# keypad.net
KiCad netlist of a schematic drawn in EAGLE
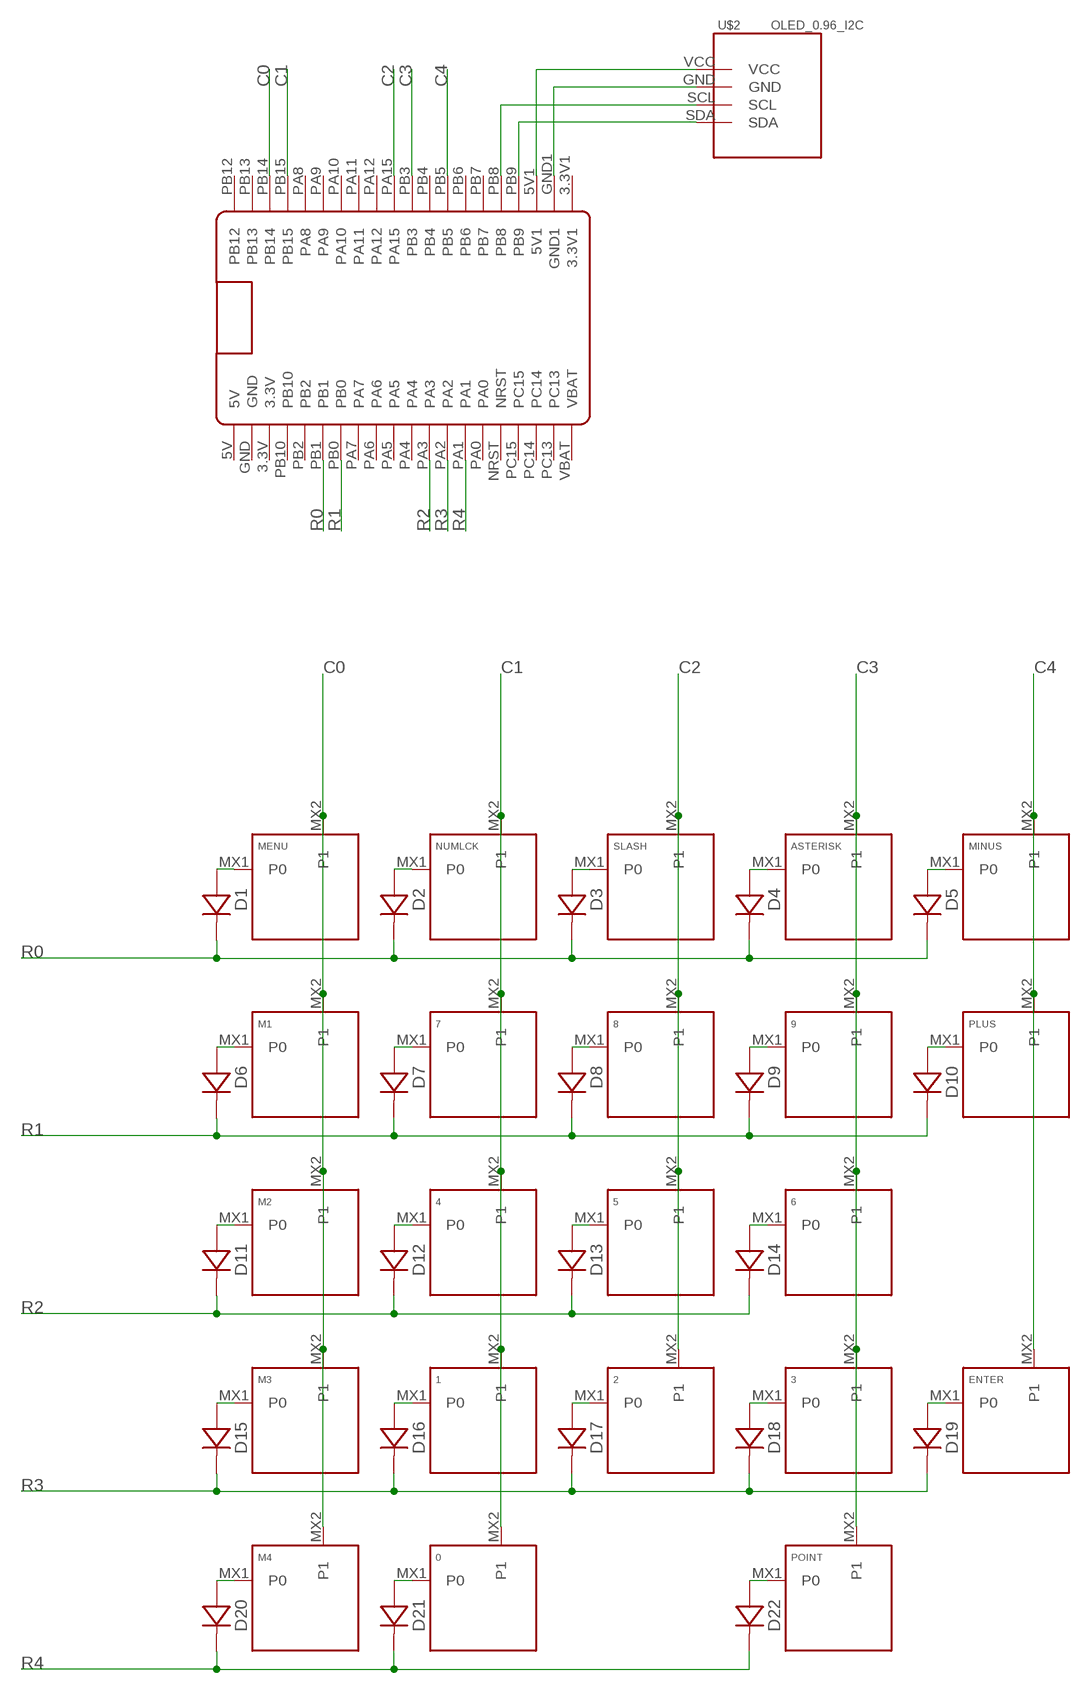
[diagram p0: schematic, sheet 1]

(export (version "E")
  (design (tool "Eeschema 10.0.6"))
  (components
    (comp (ref "0")
      (value "KEYSWITCH-PLAIN-MX-2U-FLIPPED")
      (footprint "eagle-import:MX-2U-FLIPPED")
      (libsource (lib "eagle-import") (part "KEYSWITCH-PLAIN-MX-2U-FLIPPED"))
    )
    (comp (ref "1")
      (value "KEYSWITCH-PLAIN-MX-1U")
      (footprint "eagle-import:MX-1U")
      (libsource (lib "eagle-import") (part "KEYSWITCH-PLAIN-MX-1U"))
    )
    (comp (ref "2")
      (value "KEYSWITCH-PLAIN-MX-1U")
      (footprint "eagle-import:MX-1U")
      (libsource (lib "eagle-import") (part "KEYSWITCH-PLAIN-MX-1U"))
    )
    (comp (ref "3")
      (value "KEYSWITCH-PLAIN-MX-1U")
      (footprint "eagle-import:MX-1U")
      (libsource (lib "eagle-import") (part "KEYSWITCH-PLAIN-MX-1U"))
    )
    (comp (ref "4")
      (value "KEYSWITCH-PLAIN-MX-1U")
      (footprint "eagle-import:MX-1U")
      (libsource (lib "eagle-import") (part "KEYSWITCH-PLAIN-MX-1U"))
    )
    (comp (ref "5")
      (value "KEYSWITCH-PLAIN-MX-1U")
      (footprint "eagle-import:MX-1U")
      (libsource (lib "eagle-import") (part "KEYSWITCH-PLAIN-MX-1U"))
    )
    (comp (ref "6")
      (value "KEYSWITCH-PLAIN-MX-1U")
      (footprint "eagle-import:MX-1U")
      (libsource (lib "eagle-import") (part "KEYSWITCH-PLAIN-MX-1U"))
    )
    (comp (ref "7")
      (value "KEYSWITCH-PLAIN-MX-1U")
      (footprint "eagle-import:MX-1U")
      (libsource (lib "eagle-import") (part "KEYSWITCH-PLAIN-MX-1U"))
    )
    (comp (ref "8")
      (value "KEYSWITCH-PLAIN-MX-1U")
      (footprint "eagle-import:MX-1U")
      (libsource (lib "eagle-import") (part "KEYSWITCH-PLAIN-MX-1U"))
    )
    (comp (ref "9")
      (value "KEYSWITCH-PLAIN-MX-1U")
      (footprint "eagle-import:MX-1U")
      (libsource (lib "eagle-import") (part "KEYSWITCH-PLAIN-MX-1U"))
    )
    (comp (ref "ASTERISK")
      (value "KEYSWITCH-PLAIN-MX-1U")
      (footprint "eagle-import:MX-1U")
      (libsource (lib "eagle-import") (part "KEYSWITCH-PLAIN-MX-1U"))
    )
    (comp (ref "D1")
      (value "DIODE-SOD-123")
      (footprint "eagle-import:SOD-123")
      (libsource (lib "eagle-import") (part "DIODE-SOD-123"))
    )
    (comp (ref "D2")
      (value "DIODE-SOD-123")
      (footprint "eagle-import:SOD-123")
      (libsource (lib "eagle-import") (part "DIODE-SOD-123"))
    )
    (comp (ref "D3")
      (value "DIODE-SOD-123")
      (footprint "eagle-import:SOD-123")
      (libsource (lib "eagle-import") (part "DIODE-SOD-123"))
    )
    (comp (ref "D4")
      (value "DIODE-SOD-123")
      (footprint "eagle-import:SOD-123")
      (libsource (lib "eagle-import") (part "DIODE-SOD-123"))
    )
    (comp (ref "D5")
      (value "DIODE-SOD-123")
      (footprint "eagle-import:SOD-123")
      (libsource (lib "eagle-import") (part "DIODE-SOD-123"))
    )
    (comp (ref "D6")
      (value "DIODE-SOD-123")
      (footprint "eagle-import:SOD-123")
      (libsource (lib "eagle-import") (part "DIODE-SOD-123"))
    )
    (comp (ref "D7")
      (value "DIODE-SOD-123")
      (footprint "eagle-import:SOD-123")
      (libsource (lib "eagle-import") (part "DIODE-SOD-123"))
    )
    (comp (ref "D8")
      (value "DIODE-SOD-123")
      (footprint "eagle-import:SOD-123")
      (libsource (lib "eagle-import") (part "DIODE-SOD-123"))
    )
    (comp (ref "D9")
      (value "DIODE-SOD-123")
      (footprint "eagle-import:SOD-123")
      (libsource (lib "eagle-import") (part "DIODE-SOD-123"))
    )
    (comp (ref "D10")
      (value "DIODE-SOD-123")
      (footprint "eagle-import:SOD-123")
      (libsource (lib "eagle-import") (part "DIODE-SOD-123"))
    )
    (comp (ref "D11")
      (value "DIODE-SOD-123")
      (footprint "eagle-import:SOD-123")
      (libsource (lib "eagle-import") (part "DIODE-SOD-123"))
    )
    (comp (ref "D12")
      (value "DIODE-SOD-123")
      (footprint "eagle-import:SOD-123")
      (libsource (lib "eagle-import") (part "DIODE-SOD-123"))
    )
    (comp (ref "D13")
      (value "DIODE-SOD-123")
      (footprint "eagle-import:SOD-123")
      (libsource (lib "eagle-import") (part "DIODE-SOD-123"))
    )
    (comp (ref "D14")
      (value "DIODE-SOD-123")
      (footprint "eagle-import:SOD-123")
      (libsource (lib "eagle-import") (part "DIODE-SOD-123"))
    )
    (comp (ref "D15")
      (value "DIODE-SOD-123")
      (footprint "eagle-import:SOD-123")
      (libsource (lib "eagle-import") (part "DIODE-SOD-123"))
    )
    (comp (ref "D16")
      (value "DIODE-SOD-123")
      (footprint "eagle-import:SOD-123")
      (libsource (lib "eagle-import") (part "DIODE-SOD-123"))
    )
    (comp (ref "D17")
      (value "DIODE-SOD-123")
      (footprint "eagle-import:SOD-123")
      (libsource (lib "eagle-import") (part "DIODE-SOD-123"))
    )
    (comp (ref "D18")
      (value "DIODE-SOD-123")
      (footprint "eagle-import:SOD-123")
      (libsource (lib "eagle-import") (part "DIODE-SOD-123"))
    )
    (comp (ref "D19")
      (value "DIODE-SOD-123")
      (footprint "eagle-import:SOD-123")
      (libsource (lib "eagle-import") (part "DIODE-SOD-123"))
    )
    (comp (ref "D20")
      (value "DIODE-SOD-123")
      (footprint "eagle-import:SOD-123")
      (libsource (lib "eagle-import") (part "DIODE-SOD-123"))
    )
    (comp (ref "D21")
      (value "DIODE-SOD-123")
      (footprint "eagle-import:SOD-123")
      (libsource (lib "eagle-import") (part "DIODE-SOD-123"))
    )
    (comp (ref "D22")
      (value "DIODE-SOD-123")
      (footprint "eagle-import:SOD-123")
      (libsource (lib "eagle-import") (part "DIODE-SOD-123"))
    )
    (comp (ref "ENTER")
      (value "KEYSWITCH-PLAIN-MX-2U-ROTATED")
      (footprint "eagle-import:MX-2U-ROTATED")
      (libsource (lib "eagle-import") (part "KEYSWITCH-PLAIN-MX-2U-ROTATED"))
    )
    (comp (ref "M1")
      (value "KEYSWITCH-PLAIN-MX-1U")
      (footprint "eagle-import:MX-1U")
      (libsource (lib "eagle-import") (part "KEYSWITCH-PLAIN-MX-1U"))
    )
    (comp (ref "M2")
      (value "KEYSWITCH-PLAIN-MX-1U")
      (footprint "eagle-import:MX-1U")
      (libsource (lib "eagle-import") (part "KEYSWITCH-PLAIN-MX-1U"))
    )
    (comp (ref "M3")
      (value "KEYSWITCH-PLAIN-MX-1U")
      (footprint "eagle-import:MX-1U")
      (libsource (lib "eagle-import") (part "KEYSWITCH-PLAIN-MX-1U"))
    )
    (comp (ref "M4")
      (value "KEYSWITCH-PLAIN-MX-1U")
      (footprint "eagle-import:MX-1U")
      (libsource (lib "eagle-import") (part "KEYSWITCH-PLAIN-MX-1U"))
    )
    (comp (ref "MENU")
      (value "KEYSWITCH-PLAIN-MX-1U")
      (footprint "eagle-import:MX-1U")
      (libsource (lib "eagle-import") (part "KEYSWITCH-PLAIN-MX-1U"))
    )
    (comp (ref "MINUS")
      (value "KEYSWITCH-PLAIN-MX-1U")
      (footprint "eagle-import:MX-1U")
      (libsource (lib "eagle-import") (part "KEYSWITCH-PLAIN-MX-1U"))
    )
    (comp (ref "NUMLCK")
      (value "KEYSWITCH-PLAIN-MX-1U")
      (footprint "eagle-import:MX-1U")
      (libsource (lib "eagle-import") (part "KEYSWITCH-PLAIN-MX-1U"))
    )
    (comp (ref "PLUS")
      (value "KEYSWITCH-PLAIN-MX-2U-ROTATED")
      (footprint "eagle-import:MX-2U-ROTATED")
      (libsource (lib "eagle-import") (part "KEYSWITCH-PLAIN-MX-2U-ROTATED"))
    )
    (comp (ref "POINT")
      (value "KEYSWITCH-PLAIN-MX-1U")
      (footprint "eagle-import:MX-1U")
      (libsource (lib "eagle-import") (part "KEYSWITCH-PLAIN-MX-1U"))
    )
    (comp (ref "SLASH")
      (value "KEYSWITCH-PLAIN-MX-1U")
      (footprint "eagle-import:MX-1U")
      (libsource (lib "eagle-import") (part "KEYSWITCH-PLAIN-MX-1U"))
    )
    (comp (ref "U$1")
      (value "BLACK_PILL")
      (footprint "eagle-import:BLACK_PILL")
      (libsource (lib "eagle-import") (part "BLACK_PILL"))
    )
    (comp (ref "U$2")
      (value "OLED_0.96_I2C")
      (footprint "eagle-import:OLED_0.96_I2C")
      (libsource (lib "eagle-import") (part "OLED_0.96_I2C"))
    )
  )
  (nets
    (net (code "1") (name "/5V") (class "Default")
      (node (ref "U$1") (pin "5V") (pinfunction "5V_5V") (pintype "power_in"))
    )
    (net (code "2") (name "/C0") (class "Default")
      (node (ref "M1") (pin "MX2") (pinfunction "P1_MX2") (pintype "bidirectional"))
      (node (ref "M2") (pin "MX2") (pinfunction "P1_MX2") (pintype "bidirectional"))
      (node (ref "M3") (pin "MX2") (pinfunction "P1_MX2") (pintype "bidirectional"))
      (node (ref "M4") (pin "MX2") (pinfunction "P1_MX2") (pintype "bidirectional"))
      (node (ref "MENU") (pin "MX2") (pinfunction "P1_MX2") (pintype "bidirectional"))
      (node (ref "U$1") (pin "PB14") (pinfunction "PB14_PB14") (pintype "bidirectional"))
    )
    (net (code "3") (name "/C1") (class "Default")
      (node (ref "0") (pin "MX2") (pinfunction "P1_MX2") (pintype "bidirectional"))
      (node (ref "1") (pin "MX2") (pinfunction "P1_MX2") (pintype "bidirectional"))
      (node (ref "4") (pin "MX2") (pinfunction "P1_MX2") (pintype "bidirectional"))
      (node (ref "7") (pin "MX2") (pinfunction "P1_MX2") (pintype "bidirectional"))
      (node (ref "NUMLCK") (pin "MX2") (pinfunction "P1_MX2") (pintype "bidirectional"))
      (node (ref "U$1") (pin "PB15") (pinfunction "PB15_PB15") (pintype "bidirectional"))
    )
    (net (code "4") (name "/C2") (class "Default")
      (node (ref "2") (pin "MX2") (pinfunction "P1_MX2") (pintype "bidirectional"))
      (node (ref "5") (pin "MX2") (pinfunction "P1_MX2") (pintype "bidirectional"))
      (node (ref "8") (pin "MX2") (pinfunction "P1_MX2") (pintype "bidirectional"))
      (node (ref "SLASH") (pin "MX2") (pinfunction "P1_MX2") (pintype "bidirectional"))
      (node (ref "U$1") (pin "PA15") (pinfunction "PA15_PA15") (pintype "bidirectional"))
    )
    (net (code "5") (name "/C3") (class "Default")
      (node (ref "3") (pin "MX2") (pinfunction "P1_MX2") (pintype "bidirectional"))
      (node (ref "6") (pin "MX2") (pinfunction "P1_MX2") (pintype "bidirectional"))
      (node (ref "9") (pin "MX2") (pinfunction "P1_MX2") (pintype "bidirectional"))
      (node (ref "ASTERISK") (pin "MX2") (pinfunction "P1_MX2") (pintype "bidirectional"))
      (node (ref "POINT") (pin "MX2") (pinfunction "P1_MX2") (pintype "bidirectional"))
      (node (ref "U$1") (pin "PB3") (pinfunction "PB3_PB3") (pintype "bidirectional"))
    )
    (net (code "6") (name "/C4") (class "Default")
      (node (ref "ENTER") (pin "MX2") (pinfunction "P1_MX2") (pintype "bidirectional"))
      (node (ref "MINUS") (pin "MX2") (pinfunction "P1_MX2") (pintype "bidirectional"))
      (node (ref "PLUS") (pin "MX2") (pinfunction "P1_MX2") (pintype "bidirectional"))
      (node (ref "U$1") (pin "PB5") (pinfunction "PB5_PB5") (pintype "bidirectional"))
    )
    (net (code "7") (name "/R0") (class "Default")
      (node (ref "D1") (pin "C") (pinfunction "C_C") (pintype "passive"))
      (node (ref "D2") (pin "C") (pinfunction "C_C") (pintype "passive"))
      (node (ref "D3") (pin "C") (pinfunction "C_C") (pintype "passive"))
      (node (ref "D4") (pin "C") (pinfunction "C_C") (pintype "passive"))
      (node (ref "D5") (pin "C") (pinfunction "C_C") (pintype "passive"))
      (node (ref "U$1") (pin "PB1") (pinfunction "PB1_PB1") (pintype "bidirectional"))
    )
    (net (code "8") (name "/R1") (class "Default")
      (node (ref "D10") (pin "C") (pinfunction "C_C") (pintype "passive"))
      (node (ref "D6") (pin "C") (pinfunction "C_C") (pintype "passive"))
      (node (ref "D7") (pin "C") (pinfunction "C_C") (pintype "passive"))
      (node (ref "D8") (pin "C") (pinfunction "C_C") (pintype "passive"))
      (node (ref "D9") (pin "C") (pinfunction "C_C") (pintype "passive"))
      (node (ref "U$1") (pin "PB0") (pinfunction "PB0_PB0") (pintype "bidirectional"))
    )
    (net (code "9") (name "/R2") (class "Default")
      (node (ref "D11") (pin "C") (pinfunction "C_C") (pintype "passive"))
      (node (ref "D12") (pin "C") (pinfunction "C_C") (pintype "passive"))
      (node (ref "D13") (pin "C") (pinfunction "C_C") (pintype "passive"))
      (node (ref "D14") (pin "C") (pinfunction "C_C") (pintype "passive"))
      (node (ref "U$1") (pin "PA3") (pinfunction "PA3_PA3") (pintype "bidirectional"))
    )
    (net (code "10") (name "/R3") (class "Default")
      (node (ref "D15") (pin "C") (pinfunction "C_C") (pintype "passive"))
      (node (ref "D16") (pin "C") (pinfunction "C_C") (pintype "passive"))
      (node (ref "D17") (pin "C") (pinfunction "C_C") (pintype "passive"))
      (node (ref "D18") (pin "C") (pinfunction "C_C") (pintype "passive"))
      (node (ref "D19") (pin "C") (pinfunction "C_C") (pintype "passive"))
      (node (ref "U$1") (pin "PA2") (pinfunction "PA2_PA2") (pintype "bidirectional"))
    )
    (net (code "11") (name "/R4") (class "Default")
      (node (ref "D20") (pin "C") (pinfunction "C_C") (pintype "passive"))
      (node (ref "D21") (pin "C") (pinfunction "C_C") (pintype "passive"))
      (node (ref "D22") (pin "C") (pinfunction "C_C") (pintype "passive"))
      (node (ref "U$1") (pin "PA1") (pinfunction "PA1_PA1") (pintype "bidirectional"))
    )
    (net (code "12") (name "Net-(0-P0)") (class "Default")
      (node (ref "0") (pin "MX1") (pinfunction "P0_MX1") (pintype "bidirectional"))
      (node (ref "D21") (pin "A") (pinfunction "A_A") (pintype "passive"))
    )
    (net (code "13") (name "Net-(1-P0)") (class "Default")
      (node (ref "1") (pin "MX1") (pinfunction "P0_MX1") (pintype "bidirectional"))
      (node (ref "D16") (pin "A") (pinfunction "A_A") (pintype "passive"))
    )
    (net (code "14") (name "Net-(2-P0)") (class "Default")
      (node (ref "2") (pin "MX1") (pinfunction "P0_MX1") (pintype "bidirectional"))
      (node (ref "D17") (pin "A") (pinfunction "A_A") (pintype "passive"))
    )
    (net (code "15") (name "Net-(3-P0)") (class "Default")
      (node (ref "3") (pin "MX1") (pinfunction "P0_MX1") (pintype "bidirectional"))
      (node (ref "D18") (pin "A") (pinfunction "A_A") (pintype "passive"))
    )
    (net (code "16") (name "Net-(4-P0)") (class "Default")
      (node (ref "4") (pin "MX1") (pinfunction "P0_MX1") (pintype "bidirectional"))
      (node (ref "D12") (pin "A") (pinfunction "A_A") (pintype "passive"))
    )
    (net (code "17") (name "Net-(5-P0)") (class "Default")
      (node (ref "5") (pin "MX1") (pinfunction "P0_MX1") (pintype "bidirectional"))
      (node (ref "D13") (pin "A") (pinfunction "A_A") (pintype "passive"))
    )
    (net (code "18") (name "Net-(6-P0)") (class "Default")
      (node (ref "6") (pin "MX1") (pinfunction "P0_MX1") (pintype "bidirectional"))
      (node (ref "D14") (pin "A") (pinfunction "A_A") (pintype "passive"))
    )
    (net (code "19") (name "Net-(7-P0)") (class "Default")
      (node (ref "7") (pin "MX1") (pinfunction "P0_MX1") (pintype "bidirectional"))
      (node (ref "D7") (pin "A") (pinfunction "A_A") (pintype "passive"))
    )
    (net (code "20") (name "Net-(8-P0)") (class "Default")
      (node (ref "8") (pin "MX1") (pinfunction "P0_MX1") (pintype "bidirectional"))
      (node (ref "D8") (pin "A") (pinfunction "A_A") (pintype "passive"))
    )
    (net (code "21") (name "Net-(9-P0)") (class "Default")
      (node (ref "9") (pin "MX1") (pinfunction "P0_MX1") (pintype "bidirectional"))
      (node (ref "D9") (pin "A") (pinfunction "A_A") (pintype "passive"))
    )
    (net (code "22") (name "Net-(ASTERISK-P0)") (class "Default")
      (node (ref "ASTERISK") (pin "MX1") (pinfunction "P0_MX1") (pintype "bidirectional"))
      (node (ref "D4") (pin "A") (pinfunction "A_A") (pintype "passive"))
    )
    (net (code "23") (name "Net-(ENTER-P0)") (class "Default")
      (node (ref "D19") (pin "A") (pinfunction "A_A") (pintype "passive"))
      (node (ref "ENTER") (pin "MX1") (pinfunction "P0_MX1") (pintype "bidirectional"))
    )
    (net (code "24") (name "Net-(M1-P0)") (class "Default")
      (node (ref "D6") (pin "A") (pinfunction "A_A") (pintype "passive"))
      (node (ref "M1") (pin "MX1") (pinfunction "P0_MX1") (pintype "bidirectional"))
    )
    (net (code "25") (name "Net-(M2-P0)") (class "Default")
      (node (ref "D11") (pin "A") (pinfunction "A_A") (pintype "passive"))
      (node (ref "M2") (pin "MX1") (pinfunction "P0_MX1") (pintype "bidirectional"))
    )
    (net (code "26") (name "Net-(M3-P0)") (class "Default")
      (node (ref "D15") (pin "A") (pinfunction "A_A") (pintype "passive"))
      (node (ref "M3") (pin "MX1") (pinfunction "P0_MX1") (pintype "bidirectional"))
    )
    (net (code "27") (name "Net-(M4-P0)") (class "Default")
      (node (ref "D20") (pin "A") (pinfunction "A_A") (pintype "passive"))
      (node (ref "M4") (pin "MX1") (pinfunction "P0_MX1") (pintype "bidirectional"))
    )
    (net (code "28") (name "Net-(MENU-P0)") (class "Default")
      (node (ref "D1") (pin "A") (pinfunction "A_A") (pintype "passive"))
      (node (ref "MENU") (pin "MX1") (pinfunction "P0_MX1") (pintype "bidirectional"))
    )
    (net (code "29") (name "Net-(MINUS-P0)") (class "Default")
      (node (ref "D5") (pin "A") (pinfunction "A_A") (pintype "passive"))
      (node (ref "MINUS") (pin "MX1") (pinfunction "P0_MX1") (pintype "bidirectional"))
    )
    (net (code "30") (name "Net-(NUMLCK-P0)") (class "Default")
      (node (ref "D2") (pin "A") (pinfunction "A_A") (pintype "passive"))
      (node (ref "NUMLCK") (pin "MX1") (pinfunction "P0_MX1") (pintype "bidirectional"))
    )
    (net (code "31") (name "Net-(PLUS-P0)") (class "Default")
      (node (ref "D10") (pin "A") (pinfunction "A_A") (pintype "passive"))
      (node (ref "PLUS") (pin "MX1") (pinfunction "P0_MX1") (pintype "bidirectional"))
    )
    (net (code "32") (name "Net-(POINT-P0)") (class "Default")
      (node (ref "D22") (pin "A") (pinfunction "A_A") (pintype "passive"))
      (node (ref "POINT") (pin "MX1") (pinfunction "P0_MX1") (pintype "bidirectional"))
    )
    (net (code "33") (name "Net-(SLASH-P0)") (class "Default")
      (node (ref "D3") (pin "A") (pinfunction "A_A") (pintype "passive"))
      (node (ref "SLASH") (pin "MX1") (pinfunction "P0_MX1") (pintype "bidirectional"))
    )
    (net (code "34") (name "Net-(U$1-Pad5V1)") (class "Default")
      (node (ref "U$1") (pin "5V1") (pinfunction "5V1_5V1") (pintype "bidirectional"))
      (node (ref "U$2") (pin "VCC") (pinfunction "VCC_VCC") (pintype "bidirectional"))
    )
    (net (code "35") (name "Net-(U$1-PadGND1)") (class "Default")
      (node (ref "U$1") (pin "GND1") (pinfunction "GND1_GND1") (pintype "bidirectional"))
      (node (ref "U$2") (pin "GND") (pinfunction "GND_GND") (pintype "bidirectional"))
    )
    (net (code "36") (name "Net-(U$1-PadPB8)") (class "Default")
      (node (ref "U$1") (pin "PB8") (pinfunction "PB8_PB8") (pintype "bidirectional"))
      (node (ref "U$2") (pin "SCL") (pinfunction "SCL_SCL") (pintype "bidirectional"))
    )
    (net (code "37") (name "Net-(U$1-PadPB9)") (class "Default")
      (node (ref "U$1") (pin "PB9") (pinfunction "PB9_PB9") (pintype "bidirectional"))
      (node (ref "U$2") (pin "SDA") (pinfunction "SDA_SDA") (pintype "bidirectional"))
    )
    (net (code "38") (name "unconnected-(U$1-Pad3.3V)") (class "Default")
      (node (ref "U$1") (pin "3.3V") (pinfunction "3.3V_3.3V") (pintype "bidirectional"))
    )
    (net (code "39") (name "unconnected-(U$1-Pad3.3V1)") (class "Default")
      (node (ref "U$1") (pin "3.3V1") (pinfunction "3.3V1_3.3V1") (pintype "bidirectional"))
    )
    (net (code "40") (name "unconnected-(U$1-PadGND)") (class "Default")
      (node (ref "U$1") (pin "GND") (pinfunction "GND_GND") (pintype "bidirectional"))
    )
    (net (code "41") (name "unconnected-(U$1-PadNRST)") (class "Default")
      (node (ref "U$1") (pin "NRST") (pinfunction "NRST_NRST") (pintype "bidirectional"))
    )
    (net (code "42") (name "unconnected-(U$1-PadPA0)") (class "Default")
      (node (ref "U$1") (pin "PA0") (pinfunction "PA0_PA0") (pintype "bidirectional"))
    )
    (net (code "43") (name "unconnected-(U$1-PadPA4)") (class "Default")
      (node (ref "U$1") (pin "PA4") (pinfunction "PA4_PA4") (pintype "bidirectional"))
    )
    (net (code "44") (name "unconnected-(U$1-PadPA5)") (class "Default")
      (node (ref "U$1") (pin "PA5") (pinfunction "PA5_PA5") (pintype "bidirectional"))
    )
    (net (code "45") (name "unconnected-(U$1-PadPA6)") (class "Default")
      (node (ref "U$1") (pin "PA6") (pinfunction "PA6_PA6") (pintype "bidirectional"))
    )
    (net (code "46") (name "unconnected-(U$1-PadPA7)") (class "Default")
      (node (ref "U$1") (pin "PA7") (pinfunction "PA7_PA7") (pintype "bidirectional"))
    )
    (net (code "47") (name "unconnected-(U$1-PadPA8)") (class "Default")
      (node (ref "U$1") (pin "PA8") (pinfunction "PA8_PA8") (pintype "bidirectional"))
    )
    (net (code "48") (name "unconnected-(U$1-PadPA9)") (class "Default")
      (node (ref "U$1") (pin "PA9") (pinfunction "PA9_PA9") (pintype "bidirectional"))
    )
    (net (code "49") (name "unconnected-(U$1-PadPA10)") (class "Default")
      (node (ref "U$1") (pin "PA10") (pinfunction "PA10_PA10") (pintype "bidirectional"))
    )
    (net (code "50") (name "unconnected-(U$1-PadPA11)") (class "Default")
      (node (ref "U$1") (pin "PA11") (pinfunction "PA11_PA11") (pintype "bidirectional"))
    )
    (net (code "51") (name "unconnected-(U$1-PadPA12)") (class "Default")
      (node (ref "U$1") (pin "PA12") (pinfunction "PA12_PA12") (pintype "bidirectional"))
    )
    (net (code "52") (name "unconnected-(U$1-PadPB2)") (class "Default")
      (node (ref "U$1") (pin "PB2") (pinfunction "PB2_PB2") (pintype "bidirectional"))
    )
    (net (code "53") (name "unconnected-(U$1-PadPB4)") (class "Default")
      (node (ref "U$1") (pin "PB4") (pinfunction "PB4_PB4") (pintype "bidirectional"))
    )
    (net (code "54") (name "unconnected-(U$1-PadPB6)") (class "Default")
      (node (ref "U$1") (pin "PB6") (pinfunction "PB6_PB6") (pintype "bidirectional"))
    )
    (net (code "55") (name "unconnected-(U$1-PadPB7)") (class "Default")
      (node (ref "U$1") (pin "PB7") (pinfunction "PB7_PB7") (pintype "bidirectional"))
    )
    (net (code "56") (name "unconnected-(U$1-PadPB10)") (class "Default")
      (node (ref "U$1") (pin "PB10") (pinfunction "PB10_PB10") (pintype "bidirectional"))
    )
    (net (code "57") (name "unconnected-(U$1-PadPB12)") (class "Default")
      (node (ref "U$1") (pin "PB12") (pinfunction "PB12_PB12") (pintype "bidirectional"))
    )
    (net (code "58") (name "unconnected-(U$1-PadPB13)") (class "Default")
      (node (ref "U$1") (pin "PB13") (pinfunction "PB13_PB13") (pintype "bidirectional"))
    )
    (net (code "59") (name "unconnected-(U$1-PadPC13)") (class "Default")
      (node (ref "U$1") (pin "PC13") (pinfunction "PC13_PC13") (pintype "bidirectional"))
    )
    (net (code "60") (name "unconnected-(U$1-PadPC14)") (class "Default")
      (node (ref "U$1") (pin "PC14") (pinfunction "PC14_PC14") (pintype "bidirectional"))
    )
    (net (code "61") (name "unconnected-(U$1-PadPC15)") (class "Default")
      (node (ref "U$1") (pin "PC15") (pinfunction "PC15_PC15") (pintype "bidirectional"))
    )
    (net (code "62") (name "unconnected-(U$1-PadVBAT)") (class "Default")
      (node (ref "U$1") (pin "VBAT") (pinfunction "VBAT_VBAT") (pintype "bidirectional"))
    )
  )
)
